# North_Paw_V2p0.net
KiCad netlist of a schematic drawn in EAGLE
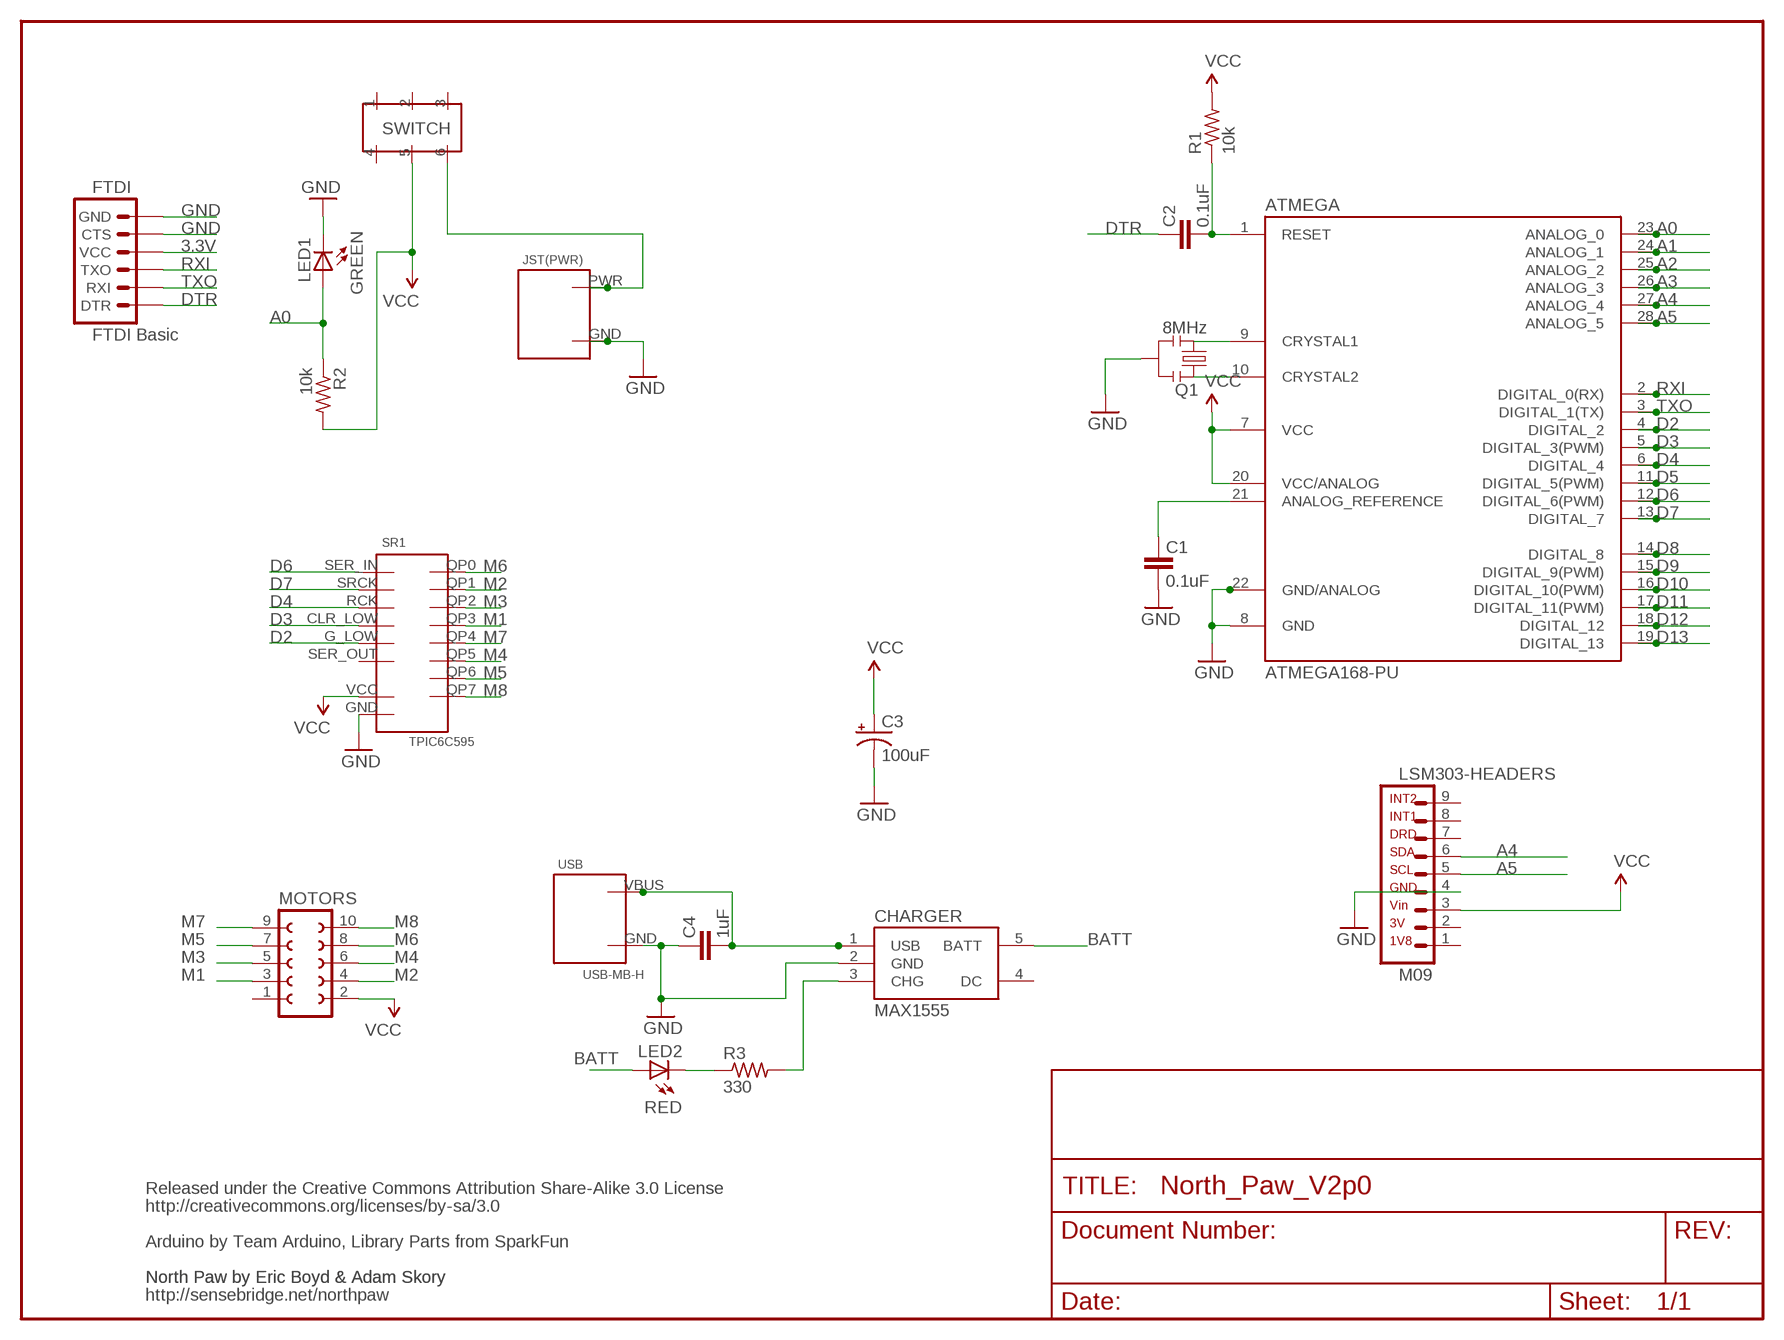
[diagram p0: schematic, sheet 1]

(export (version "E")
  (design (tool "Eeschema 10.0.6"))
  (components
    (comp (ref "ATMEGA")
      (value "ATMEGA168-PU")
      (footprint "eagle-import:DIL28-3")
      (libsource (lib "eagle-import") (part "ATMEGA168-PU"))
    )
    (comp (ref "C1")
      (value "0.1uF")
      (footprint "eagle-import:CAP-PTH-SMALL")
      (libsource (lib "eagle-import") (part "CAPPTH"))
    )
    (comp (ref "C2")
      (value "0.1uF")
      (footprint "eagle-import:CAP-PTH-SMALL")
      (libsource (lib "eagle-import") (part "CAPPTH"))
    )
    (comp (ref "C3")
      (value "100uF")
      (footprint "eagle-import:CPOL-RADIAL-100UF-25V")
      (libsource (lib "eagle-import") (part "CAP_POLPTH1"))
    )
    (comp (ref "C4")
      (value "1uF")
      (footprint "eagle-import:CAP-PTH-SMALL")
      (libsource (lib "eagle-import") (part "CAPPTH"))
    )
    (comp (ref "CHARGER")
      (value "MAX1555")
      (footprint "eagle-import:SOT23-5")
      (libsource (lib "eagle-import") (part "MAX1555"))
    )
    (comp (ref "FTDI")
      (value "FTDI Basic")
      (footprint "eagle-import:1X06")
      (libsource (lib "eagle-import") (part "ARDUINO_SERIAL_PROGRAMPTH"))
    )
    (comp (ref "JST(PWR)")
      (value "S2B-PH-K-S")
      (footprint "eagle-import:S4B-ZR")
      (libsource (lib "eagle-import") (part "S2B-PH-K-S"))
    )
    (comp (ref "LED1")
      (value "GREEN")
      (footprint "eagle-import:LED3MM")
      (libsource (lib "eagle-import") (part "LED3MM"))
    )
    (comp (ref "LED2")
      (value "RED")
      (footprint "eagle-import:LED3MM")
      (libsource (lib "eagle-import") (part "LED3MM"))
    )
    (comp (ref "LSM303-HEADERS")
      (value "M09")
      (footprint "eagle-import:MA09-1W")
      (libsource (lib "eagle-import") (part "MA09-1W"))
    )
    (comp (ref "MOTORS")
      (value "FE05-2")
      (footprint "eagle-import:FE05-2")
      (libsource (lib "eagle-import") (part "FE05-2"))
    )
    (comp (ref "Q1")
      (value "8MHz")
      (footprint "eagle-import:RESONATOR-PTH")
      (libsource (lib "eagle-import") (part "RESONATORPTH"))
    )
    (comp (ref "R1")
      (value "10k")
      (footprint "eagle-import:0204_5")
      (libsource (lib "eagle-import") (part "R-US_0204/5"))
    )
    (comp (ref "R2")
      (value "10k")
      (footprint "eagle-import:0204_7")
      (libsource (lib "eagle-import") (part "R-US_0204/7"))
    )
    (comp (ref "R3")
      (value "330")
      (footprint "eagle-import:0204_7")
      (libsource (lib "eagle-import") (part "R-US_0204/7"))
    )
    (comp (ref "SR1")
      (value "TPIC6C595")
      (footprint "eagle-import:TPIC6C595")
      (libsource (lib "eagle-import") (part "TPIC6C595"))
    )
    (comp (ref "SWITCH")
      (value "OS202011MA0QS1")
      (footprint "eagle-import:OS202011MA0QS1")
      (libsource (lib "eagle-import") (part "OS202011MA0QS1"))
    )
    (comp (ref "USB")
      (value "USB-MB-H")
      (footprint "eagle-import:USB-MB-H")
      (libsource (lib "eagle-import") (part "USB-MB-H"))
    )
  )
  (nets
    (net (code "1") (name "/1") (class "Default")
      (node (ref "SWITCH") (pin "1") (pinfunction "1_1") (pintype "power_in"))
    )
    (net (code "2") (name "/2") (class "Default")
      (node (ref "SWITCH") (pin "2") (pinfunction "2_2") (pintype "power_in"))
    )
    (net (code "3") (name "/3") (class "Default")
      (node (ref "SWITCH") (pin "3") (pinfunction "3_3") (pintype "power_in"))
    )
    (net (code "4") (name "/4") (class "Default")
      (node (ref "SWITCH") (pin "4") (pinfunction "4_4") (pintype "power_in"))
    )
    (net (code "5") (name "/A0") (class "Default")
      (node (ref "ATMEGA") (pin "23") (pinfunction "ANALOG_0_23") (pintype "bidirectional"))
      (node (ref "LED1") (pin "A") (pinfunction "A_A") (pintype "passive"))
      (node (ref "R2") (pin "1") (pinfunction "1_1") (pintype "passive"))
    )
    (net (code "6") (name "/A1") (class "Default")
      (node (ref "ATMEGA") (pin "24") (pinfunction "ANALOG_1_24") (pintype "bidirectional"))
    )
    (net (code "7") (name "/A2") (class "Default")
      (node (ref "ATMEGA") (pin "25") (pinfunction "ANALOG_2_25") (pintype "bidirectional"))
    )
    (net (code "8") (name "/A3") (class "Default")
      (node (ref "ATMEGA") (pin "26") (pinfunction "ANALOG_3_26") (pintype "bidirectional"))
    )
    (net (code "9") (name "/A4") (class "Default")
      (node (ref "ATMEGA") (pin "27") (pinfunction "ANALOG_4_27") (pintype "bidirectional"))
      (node (ref "LSM303-HEADERS") (pin "6") (pinfunction "6_6") (pintype "passive"))
    )
    (net (code "10") (name "/A5") (class "Default")
      (node (ref "ATMEGA") (pin "28") (pinfunction "ANALOG_5_28") (pintype "bidirectional"))
      (node (ref "LSM303-HEADERS") (pin "5") (pinfunction "5_5") (pintype "passive"))
    )
    (net (code "11") (name "/BATT") (class "Default")
      (node (ref "CHARGER") (pin "5") (pinfunction "BATT_5") (pintype "bidirectional"))
      (node (ref "JST(PWR)") (pin "PWR") (pinfunction "PWR_PWR") (pintype "power_in"))
      (node (ref "LED2") (pin "A") (pinfunction "A_A") (pintype "passive"))
      (node (ref "SWITCH") (pin "6") (pinfunction "6_6") (pintype "power_in"))
    )
    (net (code "12") (name "/D2") (class "Default")
      (node (ref "ATMEGA") (pin "4") (pinfunction "DIGITAL_2_4") (pintype "bidirectional"))
      (node (ref "SR1") (pin "G_LOW") (pinfunction "G_LOW_G_LOW") (pintype "input"))
    )
    (net (code "13") (name "/D3") (class "Default")
      (node (ref "ATMEGA") (pin "5") (pinfunction "DIGITAL_3(PWM)_5") (pintype "bidirectional"))
      (node (ref "SR1") (pin "CLR_LOW") (pinfunction "CLR_LOW_CLR_LOW") (pintype "input"))
    )
    (net (code "14") (name "/D4") (class "Default")
      (node (ref "ATMEGA") (pin "6") (pinfunction "DIGITAL_4_6") (pintype "bidirectional"))
      (node (ref "SR1") (pin "RCK") (pinfunction "RCK_RCK") (pintype "input"))
    )
    (net (code "15") (name "/D5") (class "Default")
      (node (ref "ATMEGA") (pin "11") (pinfunction "DIGITAL_5(PWM)_11") (pintype "bidirectional"))
    )
    (net (code "16") (name "/D6") (class "Default")
      (node (ref "ATMEGA") (pin "12") (pinfunction "DIGITAL_6(PWM)_12") (pintype "bidirectional"))
      (node (ref "SR1") (pin "SER_IN") (pinfunction "SER_IN_SER_IN") (pintype "input"))
    )
    (net (code "17") (name "/D7") (class "Default")
      (node (ref "ATMEGA") (pin "13") (pinfunction "DIGITAL_7_13") (pintype "bidirectional"))
      (node (ref "SR1") (pin "SRCK") (pinfunction "SRCK_SRCK") (pintype "input"))
    )
    (net (code "18") (name "/D8") (class "Default")
      (node (ref "ATMEGA") (pin "14") (pinfunction "DIGITAL_8_14") (pintype "bidirectional"))
    )
    (net (code "19") (name "/D9") (class "Default")
      (node (ref "ATMEGA") (pin "15") (pinfunction "DIGITAL_9(PWM)_15") (pintype "bidirectional"))
    )
    (net (code "20") (name "/D10") (class "Default")
      (node (ref "ATMEGA") (pin "16") (pinfunction "DIGITAL_10(PWM)_16") (pintype "bidirectional"))
    )
    (net (code "21") (name "/D11") (class "Default")
      (node (ref "ATMEGA") (pin "17") (pinfunction "DIGITAL_11(PWM)_17") (pintype "bidirectional"))
    )
    (net (code "22") (name "/D12") (class "Default")
      (node (ref "ATMEGA") (pin "18") (pinfunction "DIGITAL_12_18") (pintype "bidirectional"))
    )
    (net (code "23") (name "/D13") (class "Default")
      (node (ref "ATMEGA") (pin "19") (pinfunction "DIGITAL_13_19") (pintype "bidirectional"))
    )
    (net (code "24") (name "/DTR") (class "Default")
      (node (ref "C2") (pin "2") (pinfunction "2_2") (pintype "passive"))
      (node (ref "FTDI") (pin "1") (pinfunction "DTR_1") (pintype "passive"))
    )
    (net (code "25") (name "/M1") (class "Default")
      (node (ref "MOTORS") (pin "3") (pinfunction "3_3") (pintype "passive"))
      (node (ref "SR1") (pin "QP3") (pinfunction "QP3_QP3") (pintype "output"))
    )
    (net (code "26") (name "/M2") (class "Default")
      (node (ref "MOTORS") (pin "4") (pinfunction "4_4") (pintype "passive"))
      (node (ref "SR1") (pin "QP1") (pinfunction "QP1_QP1") (pintype "output"))
    )
    (net (code "27") (name "/M3") (class "Default")
      (node (ref "MOTORS") (pin "5") (pinfunction "5_5") (pintype "passive"))
      (node (ref "SR1") (pin "QP2") (pinfunction "QP2_QP2") (pintype "output"))
    )
    (net (code "28") (name "/M4") (class "Default")
      (node (ref "MOTORS") (pin "6") (pinfunction "6_6") (pintype "passive"))
      (node (ref "SR1") (pin "QP5") (pinfunction "QP5_QP5") (pintype "output"))
    )
    (net (code "29") (name "/M5") (class "Default")
      (node (ref "MOTORS") (pin "7") (pinfunction "7_7") (pintype "passive"))
      (node (ref "SR1") (pin "QP6") (pinfunction "QP6_QP6") (pintype "output"))
    )
    (net (code "30") (name "/M6") (class "Default")
      (node (ref "MOTORS") (pin "8") (pinfunction "8_8") (pintype "passive"))
      (node (ref "SR1") (pin "QP0") (pinfunction "QP0_QP0") (pintype "output"))
    )
    (net (code "31") (name "/M7") (class "Default")
      (node (ref "MOTORS") (pin "9") (pinfunction "9_9") (pintype "passive"))
      (node (ref "SR1") (pin "QP4") (pinfunction "QP4_QP4") (pintype "output"))
    )
    (net (code "32") (name "/M8") (class "Default")
      (node (ref "MOTORS") (pin "10") (pinfunction "10_10") (pintype "passive"))
      (node (ref "SR1") (pin "QP7") (pinfunction "QP7_QP7") (pintype "output"))
    )
    (net (code "33") (name "/RXI") (class "Default")
      (node (ref "ATMEGA") (pin "2") (pinfunction "DIGITAL_0(RX)_2") (pintype "bidirectional"))
      (node (ref "FTDI") (pin "3") (pinfunction "TXO_3") (pintype "passive"))
    )
    (net (code "34") (name "/TXO") (class "Default")
      (node (ref "ATMEGA") (pin "3") (pinfunction "DIGITAL_1(TX)_3") (pintype "bidirectional"))
      (node (ref "FTDI") (pin "2") (pinfunction "RXI_2") (pintype "passive"))
    )
    (net (code "35") (name "GND") (class "Default")
      (node (ref "ATMEGA") (pin "22") (pinfunction "GND/ANALOG_22") (pintype "power_in"))
      (node (ref "ATMEGA") (pin "8") (pinfunction "GND_8") (pintype "power_in"))
      (node (ref "C1") (pin "1") (pinfunction "1_1") (pintype "passive"))
      (node (ref "C3") (pin "2") (pinfunction "-_2") (pintype "passive"))
      (node (ref "C4") (pin "2") (pinfunction "2_2") (pintype "passive"))
      (node (ref "CHARGER") (pin "2") (pinfunction "GND_2") (pintype "bidirectional"))
      (node (ref "FTDI") (pin "5") (pinfunction "CTS_5") (pintype "passive"))
      (node (ref "FTDI") (pin "6") (pinfunction "GND_6") (pintype "passive"))
      (node (ref "JST(PWR)") (pin "GND") (pinfunction "GND_GND") (pintype "power_in"))
      (node (ref "LED1") (pin "K") (pinfunction "C_K") (pintype "passive"))
      (node (ref "LSM303-HEADERS") (pin "4") (pinfunction "4_4") (pintype "passive"))
      (node (ref "Q1") (pin "2") (pinfunction "2_2") (pintype "passive"))
      (node (ref "SR1") (pin "GND") (pinfunction "GND_GND") (pintype "power_in"))
      (node (ref "USB") (pin "GND") (pinfunction "GND_GND") (pintype "power_in"))
    )
    (net (code "36") (name "Net-(ATMEGA-ANALOG_REFERENCE)") (class "Default")
      (node (ref "ATMEGA") (pin "21") (pinfunction "ANALOG_REFERENCE_21") (pintype "passive"))
      (node (ref "C1") (pin "2") (pinfunction "2_2") (pintype "passive"))
    )
    (net (code "37") (name "Net-(ATMEGA-CRYSTAL1)") (class "Default")
      (node (ref "ATMEGA") (pin "9") (pinfunction "CRYSTAL1_9") (pintype "bidirectional"))
      (node (ref "Q1") (pin "3") (pinfunction "3_3") (pintype "passive"))
    )
    (net (code "38") (name "Net-(ATMEGA-CRYSTAL2)") (class "Default")
      (node (ref "ATMEGA") (pin "10") (pinfunction "CRYSTAL2_10") (pintype "bidirectional"))
      (node (ref "Q1") (pin "1") (pinfunction "1_1") (pintype "passive"))
    )
    (net (code "39") (name "Net-(ATMEGA-RESET)") (class "Default")
      (node (ref "ATMEGA") (pin "1") (pinfunction "RESET_1") (pintype "bidirectional"))
      (node (ref "C2") (pin "1") (pinfunction "1_1") (pintype "passive"))
      (node (ref "R1") (pin "1") (pinfunction "1_1") (pintype "passive"))
    )
    (net (code "40") (name "Net-(CHARGER-CHG)") (class "Default")
      (node (ref "CHARGER") (pin "3") (pinfunction "CHG_3") (pintype "bidirectional"))
      (node (ref "R3") (pin "2") (pinfunction "2_2") (pintype "passive"))
    )
    (net (code "41") (name "Net-(CHARGER-USB)") (class "Default")
      (node (ref "C4") (pin "1") (pinfunction "1_1") (pintype "passive"))
      (node (ref "CHARGER") (pin "1") (pinfunction "USB_1") (pintype "bidirectional"))
      (node (ref "USB") (pin "VBUS") (pinfunction "PWR_VBUS") (pintype "power_in"))
    )
    (net (code "42") (name "Net-(LED2-C)") (class "Default")
      (node (ref "LED2") (pin "K") (pinfunction "C_K") (pintype "passive"))
      (node (ref "R3") (pin "1") (pinfunction "1_1") (pintype "passive"))
    )
    (net (code "43") (name "VCC") (class "Default")
      (node (ref "ATMEGA") (pin "20") (pinfunction "VCC/ANALOG_20") (pintype "passive"))
      (node (ref "ATMEGA") (pin "7") (pinfunction "VCC_7") (pintype "power_in"))
      (node (ref "C3") (pin "1") (pinfunction "+_1") (pintype "passive"))
      (node (ref "FTDI") (pin "4") (pinfunction "VCC_4") (pintype "passive"))
      (node (ref "LSM303-HEADERS") (pin "3") (pinfunction "3_3") (pintype "passive"))
      (node (ref "MOTORS") (pin "2") (pinfunction "2_2") (pintype "passive"))
      (node (ref "R1") (pin "2") (pinfunction "2_2") (pintype "passive"))
      (node (ref "R2") (pin "2") (pinfunction "2_2") (pintype "passive"))
      (node (ref "SR1") (pin "VCC") (pinfunction "VCC_VCC") (pintype "power_in"))
      (node (ref "SWITCH") (pin "5") (pinfunction "5_5") (pintype "power_in"))
    )
    (net (code "44") (name "unconnected-(CHARGER-DC-Pad4)") (class "Default")
      (node (ref "CHARGER") (pin "4") (pinfunction "DC_4") (pintype "bidirectional"))
    )
    (net (code "45") (name "unconnected-(LSM303-HEADERS-Pad1)") (class "Default")
      (node (ref "LSM303-HEADERS") (pin "1") (pinfunction "1_1") (pintype "passive"))
    )
    (net (code "46") (name "unconnected-(LSM303-HEADERS-Pad2)") (class "Default")
      (node (ref "LSM303-HEADERS") (pin "2") (pinfunction "2_2") (pintype "passive"))
    )
    (net (code "47") (name "unconnected-(LSM303-HEADERS-Pad7)") (class "Default")
      (node (ref "LSM303-HEADERS") (pin "7") (pinfunction "7_7") (pintype "passive"))
    )
    (net (code "48") (name "unconnected-(LSM303-HEADERS-Pad8)") (class "Default")
      (node (ref "LSM303-HEADERS") (pin "8") (pinfunction "8_8") (pintype "passive"))
    )
    (net (code "49") (name "unconnected-(LSM303-HEADERS-Pad9)") (class "Default")
      (node (ref "LSM303-HEADERS") (pin "9") (pinfunction "9_9") (pintype "passive"))
    )
    (net (code "50") (name "unconnected-(MOTORS-Pad1)") (class "Default")
      (node (ref "MOTORS") (pin "1") (pinfunction "1_1") (pintype "passive"))
    )
    (net (code "51") (name "unconnected-(SR1-PadSER_OUT)") (class "Default")
      (node (ref "SR1") (pin "SER_OUT") (pinfunction "SER_OUT_SER_OUT") (pintype "output"))
    )
  )
)
